# breakout-rv-rtc.net
KiCad netlist of a schematic drawn in EAGLE
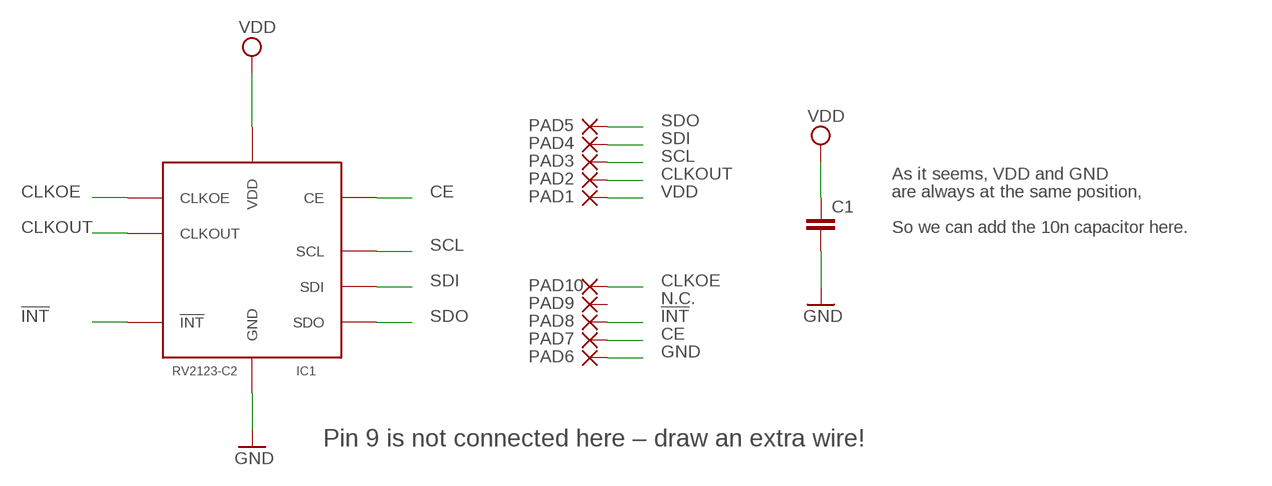
[diagram p0: schematic, sheet 1]

(export (version "E")
  (design (tool "Eeschema 10.0.6"))
  (components
    (comp (ref "C1")
      (value "C-EUC0805K")
      (footprint "eagle-import:C0805K")
      (libsource (lib "eagle-import") (part "C-EUC0805K"))
    )
    (comp (ref "IC1")
      (value "RV2123-C2")
      (footprint "eagle-import:SON_10-PIN")
      (libsource (lib "eagle-import") (part "RV2123-C2"))
    )
    (comp (ref "PAD1")
      (value "1,6/0,8")
      (footprint "eagle-import:1,6_0,8")
      (libsource (lib "eagle-import") (part "1,6/0,8"))
    )
    (comp (ref "PAD2")
      (value "1,6/0,8")
      (footprint "eagle-import:1,6_0,8")
      (libsource (lib "eagle-import") (part "1,6/0,8"))
    )
    (comp (ref "PAD3")
      (value "1,6/0,8")
      (footprint "eagle-import:1,6_0,8")
      (libsource (lib "eagle-import") (part "1,6/0,8"))
    )
    (comp (ref "PAD4")
      (value "1,6/0,8")
      (footprint "eagle-import:1,6_0,8")
      (libsource (lib "eagle-import") (part "1,6/0,8"))
    )
    (comp (ref "PAD5")
      (value "1,6/0,8")
      (footprint "eagle-import:1,6_0,8")
      (libsource (lib "eagle-import") (part "1,6/0,8"))
    )
    (comp (ref "PAD6")
      (value "1,6/0,8")
      (footprint "eagle-import:1,6_0,8")
      (libsource (lib "eagle-import") (part "1,6/0,8"))
    )
    (comp (ref "PAD7")
      (value "1,6/0,8")
      (footprint "eagle-import:1,6_0,8")
      (libsource (lib "eagle-import") (part "1,6/0,8"))
    )
    (comp (ref "PAD8")
      (value "1,6/0,8")
      (footprint "eagle-import:1,6_0,8")
      (libsource (lib "eagle-import") (part "1,6/0,8"))
    )
    (comp (ref "PAD9")
      (value "1,6/0,8")
      (footprint "eagle-import:1,6_0,8")
      (libsource (lib "eagle-import") (part "1,6/0,8"))
    )
    (comp (ref "PAD10")
      (value "1,6/0,8")
      (footprint "eagle-import:1,6_0,8")
      (libsource (lib "eagle-import") (part "1,6/0,8"))
    )
  )
  (nets
    (net (code "1") (name "/CE") (class "Default")
      (node (ref "IC1") (pin "P.7") (pinfunction "CE_P.7") (pintype "input"))
      (node (ref "PAD7") (pin "1") (pinfunction "P_1") (pintype "passive"))
    )
    (net (code "2") (name "/CLKOE") (class "Default")
      (node (ref "IC1") (pin "P.10") (pinfunction "CLKOE_P.10") (pintype "input"))
      (node (ref "PAD10") (pin "1") (pinfunction "P_1") (pintype "passive"))
    )
    (net (code "3") (name "/CLKOUT") (class "Default")
      (node (ref "IC1") (pin "P.2") (pinfunction "CLKOUT_P.2") (pintype "open_collector"))
      (node (ref "PAD2") (pin "1") (pinfunction "P_1") (pintype "passive"))
    )
    (net (code "4") (name "/SCL") (class "Default")
      (node (ref "IC1") (pin "P.3") (pinfunction "SCL_P.3") (pintype "tri_state"))
      (node (ref "PAD3") (pin "1") (pinfunction "P_1") (pintype "passive"))
    )
    (net (code "5") (name "/SDI") (class "Default")
      (node (ref "IC1") (pin "P.4") (pinfunction "SDI_P.4") (pintype "tri_state"))
      (node (ref "PAD4") (pin "1") (pinfunction "P_1") (pintype "passive"))
    )
    (net (code "6") (name "/SDO") (class "Default")
      (node (ref "IC1") (pin "P.5") (pinfunction "SDO_P.5") (pintype "tri_state"))
      (node (ref "PAD5") (pin "1") (pinfunction "P_1") (pintype "passive"))
    )
    (net (code "7") (name "/~{INT}") (class "Default")
      (node (ref "IC1") (pin "P.8") (pinfunction "~{INT}_P.8") (pintype "open_collector"))
      (node (ref "PAD8") (pin "1") (pinfunction "P_1") (pintype "passive"))
    )
    (net (code "8") (name "GND") (class "Default")
      (node (ref "C1") (pin "2") (pinfunction "2_2") (pintype "passive"))
      (node (ref "IC1") (pin "P.6") (pinfunction "GND_P.6") (pintype "power_in"))
      (node (ref "PAD6") (pin "1") (pinfunction "P_1") (pintype "passive"))
    )
    (net (code "9") (name "VDD") (class "Default")
      (node (ref "C1") (pin "1") (pinfunction "1_1") (pintype "passive"))
      (node (ref "IC1") (pin "P.1") (pinfunction "VDD_P.1") (pintype "power_in"))
      (node (ref "PAD1") (pin "1") (pinfunction "P_1") (pintype "passive"))
    )
    (net (code "10") (name "unconnected-(PAD9-P-Pad1)") (class "Default")
      (node (ref "PAD9") (pin "1") (pinfunction "P_1") (pintype "passive"))
    )
  )
)
